# S151D.net
KiCad netlist of a schematic drawn in EAGLE
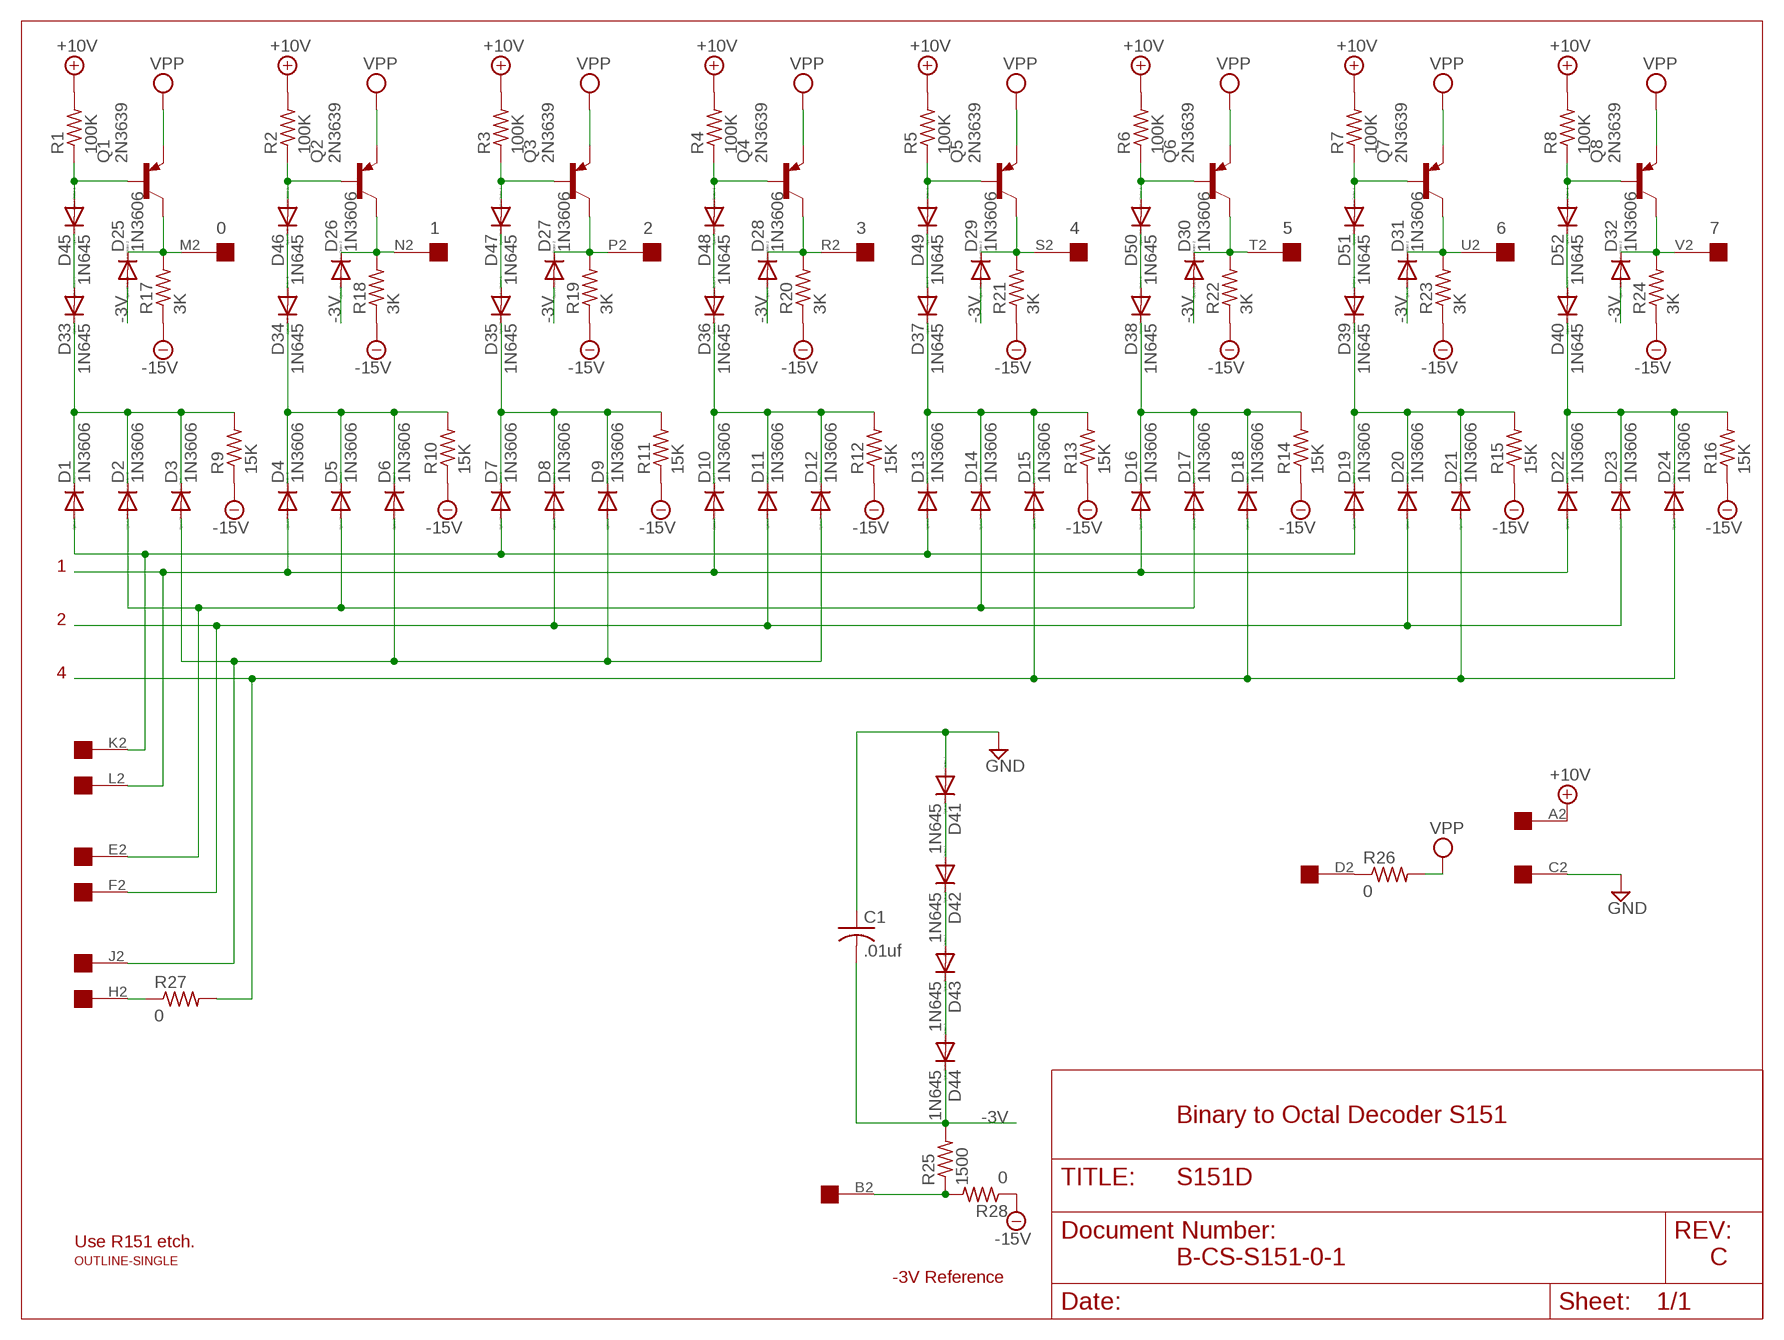
[diagram p0: schematic, sheet 1]

(export (version "E")
  (design (tool "Eeschema 10.0.6"))
  (components
    (comp (ref "C1")
      (value ".01uf")
      (footprint "eagle-import:C050-025X075")
      (libsource (lib "eagle-import") (part "C-US050-025X075"))
    )
    (comp (ref "D1")
      (value "1N3606")
      (footprint "eagle-import:DO35-10")
      (libsource (lib "eagle-import") (part "1N4148DO35-10"))
    )
    (comp (ref "D2")
      (value "1N3606")
      (footprint "eagle-import:DO35-10")
      (libsource (lib "eagle-import") (part "1N4148DO35-10"))
    )
    (comp (ref "D3")
      (value "1N3606")
      (footprint "eagle-import:DO35-10")
      (libsource (lib "eagle-import") (part "1N4148DO35-10"))
    )
    (comp (ref "D4")
      (value "1N3606")
      (footprint "eagle-import:DO35-10")
      (libsource (lib "eagle-import") (part "1N4148DO35-10"))
    )
    (comp (ref "D5")
      (value "1N3606")
      (footprint "eagle-import:DO35-10")
      (libsource (lib "eagle-import") (part "1N4148DO35-10"))
    )
    (comp (ref "D6")
      (value "1N3606")
      (footprint "eagle-import:DO35-10")
      (libsource (lib "eagle-import") (part "1N4148DO35-10"))
    )
    (comp (ref "D7")
      (value "1N3606")
      (footprint "eagle-import:DO35-10")
      (libsource (lib "eagle-import") (part "1N4148DO35-10"))
    )
    (comp (ref "D8")
      (value "1N3606")
      (footprint "eagle-import:DO35-10")
      (libsource (lib "eagle-import") (part "1N4148DO35-10"))
    )
    (comp (ref "D9")
      (value "1N3606")
      (footprint "eagle-import:DO35-10")
      (libsource (lib "eagle-import") (part "1N4148DO35-10"))
    )
    (comp (ref "D10")
      (value "1N3606")
      (footprint "eagle-import:DO35-10")
      (libsource (lib "eagle-import") (part "1N4148DO35-10"))
    )
    (comp (ref "D11")
      (value "1N3606")
      (footprint "eagle-import:DO35-10")
      (libsource (lib "eagle-import") (part "1N4148DO35-10"))
    )
    (comp (ref "D12")
      (value "1N3606")
      (footprint "eagle-import:DO35-10")
      (libsource (lib "eagle-import") (part "1N4148DO35-10"))
    )
    (comp (ref "D13")
      (value "1N3606")
      (footprint "eagle-import:DO35-10")
      (libsource (lib "eagle-import") (part "1N4148DO35-10"))
    )
    (comp (ref "D14")
      (value "1N3606")
      (footprint "eagle-import:DO35-10")
      (libsource (lib "eagle-import") (part "1N4148DO35-10"))
    )
    (comp (ref "D15")
      (value "1N3606")
      (footprint "eagle-import:DO35-10")
      (libsource (lib "eagle-import") (part "1N4148DO35-10"))
    )
    (comp (ref "D16")
      (value "1N3606")
      (footprint "eagle-import:DO35-10")
      (libsource (lib "eagle-import") (part "1N4148DO35-10"))
    )
    (comp (ref "D17")
      (value "1N3606")
      (footprint "eagle-import:DO35-10")
      (libsource (lib "eagle-import") (part "1N4148DO35-10"))
    )
    (comp (ref "D18")
      (value "1N3606")
      (footprint "eagle-import:DO35-10")
      (libsource (lib "eagle-import") (part "1N4148DO35-10"))
    )
    (comp (ref "D19")
      (value "1N3606")
      (footprint "eagle-import:DO35-10")
      (libsource (lib "eagle-import") (part "1N4148DO35-10"))
    )
    (comp (ref "D20")
      (value "1N3606")
      (footprint "eagle-import:DO35-10")
      (libsource (lib "eagle-import") (part "1N4148DO35-10"))
    )
    (comp (ref "D21")
      (value "1N3606")
      (footprint "eagle-import:DO35-10")
      (libsource (lib "eagle-import") (part "1N4148DO35-10"))
    )
    (comp (ref "D22")
      (value "1N3606")
      (footprint "eagle-import:DO35-10")
      (libsource (lib "eagle-import") (part "1N4148DO35-10"))
    )
    (comp (ref "D23")
      (value "1N3606")
      (footprint "eagle-import:DO35-10")
      (libsource (lib "eagle-import") (part "1N4148DO35-10"))
    )
    (comp (ref "D24")
      (value "1N3606")
      (footprint "eagle-import:DO35-10")
      (libsource (lib "eagle-import") (part "1N4148DO35-10"))
    )
    (comp (ref "D25")
      (value "1N3606")
      (footprint "eagle-import:DO35-10")
      (libsource (lib "eagle-import") (part "1N4148DO35-10"))
    )
    (comp (ref "D26")
      (value "1N3606")
      (footprint "eagle-import:DO35-10")
      (libsource (lib "eagle-import") (part "1N4148DO35-10"))
    )
    (comp (ref "D27")
      (value "1N3606")
      (footprint "eagle-import:DO35-10")
      (libsource (lib "eagle-import") (part "1N4148DO35-10"))
    )
    (comp (ref "D28")
      (value "1N3606")
      (footprint "eagle-import:DO35-10")
      (libsource (lib "eagle-import") (part "1N4148DO35-10"))
    )
    (comp (ref "D29")
      (value "1N3606")
      (footprint "eagle-import:DO35-10")
      (libsource (lib "eagle-import") (part "1N4148DO35-10"))
    )
    (comp (ref "D30")
      (value "1N3606")
      (footprint "eagle-import:DO35-10")
      (libsource (lib "eagle-import") (part "1N4148DO35-10"))
    )
    (comp (ref "D31")
      (value "1N3606")
      (footprint "eagle-import:DO35-10")
      (libsource (lib "eagle-import") (part "1N4148DO35-10"))
    )
    (comp (ref "D32")
      (value "1N3606")
      (footprint "eagle-import:DO35-10")
      (libsource (lib "eagle-import") (part "1N4148DO35-10"))
    )
    (comp (ref "D33")
      (value "1N645")
      (footprint "eagle-import:DO35-10")
      (libsource (lib "eagle-import") (part "1N4148DO35-10"))
    )
    (comp (ref "D34")
      (value "1N645")
      (footprint "eagle-import:DO35-10")
      (libsource (lib "eagle-import") (part "1N4148DO35-10"))
    )
    (comp (ref "D35")
      (value "1N645")
      (footprint "eagle-import:DO35-10")
      (libsource (lib "eagle-import") (part "1N4148DO35-10"))
    )
    (comp (ref "D36")
      (value "1N645")
      (footprint "eagle-import:DO35-10")
      (libsource (lib "eagle-import") (part "1N4148DO35-10"))
    )
    (comp (ref "D37")
      (value "1N645")
      (footprint "eagle-import:DO35-10")
      (libsource (lib "eagle-import") (part "1N4148DO35-10"))
    )
    (comp (ref "D38")
      (value "1N645")
      (footprint "eagle-import:DO35-10")
      (libsource (lib "eagle-import") (part "1N4148DO35-10"))
    )
    (comp (ref "D39")
      (value "1N645")
      (footprint "eagle-import:DO35-10")
      (libsource (lib "eagle-import") (part "1N4148DO35-10"))
    )
    (comp (ref "D40")
      (value "1N645")
      (footprint "eagle-import:DO35-10")
      (libsource (lib "eagle-import") (part "1N4148DO35-10"))
    )
    (comp (ref "D41")
      (value "1N645")
      (footprint "eagle-import:DO35-10")
      (libsource (lib "eagle-import") (part "1N4148DO35-10"))
    )
    (comp (ref "D42")
      (value "1N645")
      (footprint "eagle-import:DO35-10")
      (libsource (lib "eagle-import") (part "1N4148DO35-10"))
    )
    (comp (ref "D43")
      (value "1N645")
      (footprint "eagle-import:DO35-10")
      (libsource (lib "eagle-import") (part "1N4148DO35-10"))
    )
    (comp (ref "D44")
      (value "1N645")
      (footprint "eagle-import:DO35-10")
      (libsource (lib "eagle-import") (part "1N4148DO35-10"))
    )
    (comp (ref "D45")
      (value "1N645")
      (footprint "eagle-import:DO35-10")
      (libsource (lib "eagle-import") (part "1N4148DO35-10"))
    )
    (comp (ref "D46")
      (value "1N645")
      (footprint "eagle-import:DO35-10")
      (libsource (lib "eagle-import") (part "1N4148DO35-10"))
    )
    (comp (ref "D47")
      (value "1N645")
      (footprint "eagle-import:DO35-10")
      (libsource (lib "eagle-import") (part "1N4148DO35-10"))
    )
    (comp (ref "D48")
      (value "1N645")
      (footprint "eagle-import:DO35-10")
      (libsource (lib "eagle-import") (part "1N4148DO35-10"))
    )
    (comp (ref "D49")
      (value "1N645")
      (footprint "eagle-import:DO35-10")
      (libsource (lib "eagle-import") (part "1N4148DO35-10"))
    )
    (comp (ref "D50")
      (value "1N645")
      (footprint "eagle-import:DO35-10")
      (libsource (lib "eagle-import") (part "1N4148DO35-10"))
    )
    (comp (ref "D51")
      (value "1N645")
      (footprint "eagle-import:DO35-10")
      (libsource (lib "eagle-import") (part "1N4148DO35-10"))
    )
    (comp (ref "D52")
      (value "1N645")
      (footprint "eagle-import:DO35-10")
      (libsource (lib "eagle-import") (part "1N4148DO35-10"))
    )
    (comp (ref "Q1")
      (value "2N3639")
      (footprint "eagle-import:TO39")
      (libsource (lib "eagle-import") (part "2N3637"))
    )
    (comp (ref "Q2")
      (value "2N3639")
      (footprint "eagle-import:TO39")
      (libsource (lib "eagle-import") (part "2N3637"))
    )
    (comp (ref "Q3")
      (value "2N3639")
      (footprint "eagle-import:TO39")
      (libsource (lib "eagle-import") (part "2N3637"))
    )
    (comp (ref "Q4")
      (value "2N3639")
      (footprint "eagle-import:TO39")
      (libsource (lib "eagle-import") (part "2N3637"))
    )
    (comp (ref "Q5")
      (value "2N3639")
      (footprint "eagle-import:TO39")
      (libsource (lib "eagle-import") (part "2N3637"))
    )
    (comp (ref "Q6")
      (value "2N3639")
      (footprint "eagle-import:TO39")
      (libsource (lib "eagle-import") (part "2N3637"))
    )
    (comp (ref "Q7")
      (value "2N3639")
      (footprint "eagle-import:TO39")
      (libsource (lib "eagle-import") (part "2N3637"))
    )
    (comp (ref "Q8")
      (value "2N3639")
      (footprint "eagle-import:TO39")
      (libsource (lib "eagle-import") (part "2N3637"))
    )
    (comp (ref "R1")
      (value "100K")
      (footprint "eagle-import:0207_10")
      (libsource (lib "eagle-import") (part "R-US_0207/10"))
    )
    (comp (ref "R2")
      (value "100K")
      (footprint "eagle-import:0207_10")
      (libsource (lib "eagle-import") (part "R-US_0207/10"))
    )
    (comp (ref "R3")
      (value "100K")
      (footprint "eagle-import:0207_10")
      (libsource (lib "eagle-import") (part "R-US_0207/10"))
    )
    (comp (ref "R4")
      (value "100K")
      (footprint "eagle-import:0207_10")
      (libsource (lib "eagle-import") (part "R-US_0207/10"))
    )
    (comp (ref "R5")
      (value "100K")
      (footprint "eagle-import:0207_10")
      (libsource (lib "eagle-import") (part "R-US_0207/10"))
    )
    (comp (ref "R6")
      (value "100K")
      (footprint "eagle-import:0207_10")
      (libsource (lib "eagle-import") (part "R-US_0207/10"))
    )
    (comp (ref "R7")
      (value "100K")
      (footprint "eagle-import:0207_10")
      (libsource (lib "eagle-import") (part "R-US_0207/10"))
    )
    (comp (ref "R8")
      (value "100K")
      (footprint "eagle-import:0207_10")
      (libsource (lib "eagle-import") (part "R-US_0207/10"))
    )
    (comp (ref "R9")
      (value "15K")
      (footprint "eagle-import:0207_10")
      (libsource (lib "eagle-import") (part "R-US_0207/10"))
    )
    (comp (ref "R10")
      (value "15K")
      (footprint "eagle-import:0207_10")
      (libsource (lib "eagle-import") (part "R-US_0207/10"))
    )
    (comp (ref "R11")
      (value "15K")
      (footprint "eagle-import:0207_10")
      (libsource (lib "eagle-import") (part "R-US_0207/10"))
    )
    (comp (ref "R12")
      (value "15K")
      (footprint "eagle-import:0207_10")
      (libsource (lib "eagle-import") (part "R-US_0207/10"))
    )
    (comp (ref "R13")
      (value "15K")
      (footprint "eagle-import:0207_10")
      (libsource (lib "eagle-import") (part "R-US_0207/10"))
    )
    (comp (ref "R14")
      (value "15K")
      (footprint "eagle-import:0207_10")
      (libsource (lib "eagle-import") (part "R-US_0207/10"))
    )
    (comp (ref "R15")
      (value "15K")
      (footprint "eagle-import:0207_10")
      (libsource (lib "eagle-import") (part "R-US_0207/10"))
    )
    (comp (ref "R16")
      (value "15K")
      (footprint "eagle-import:0207_10")
      (libsource (lib "eagle-import") (part "R-US_0207/10"))
    )
    (comp (ref "R17")
      (value "3K")
      (footprint "eagle-import:0207_10")
      (libsource (lib "eagle-import") (part "R-US_0207/10"))
    )
    (comp (ref "R18")
      (value "3K")
      (footprint "eagle-import:0207_10")
      (libsource (lib "eagle-import") (part "R-US_0207/10"))
    )
    (comp (ref "R19")
      (value "3K")
      (footprint "eagle-import:0207_10")
      (libsource (lib "eagle-import") (part "R-US_0207/10"))
    )
    (comp (ref "R20")
      (value "3K")
      (footprint "eagle-import:0207_10")
      (libsource (lib "eagle-import") (part "R-US_0207/10"))
    )
    (comp (ref "R21")
      (value "3K")
      (footprint "eagle-import:0207_10")
      (libsource (lib "eagle-import") (part "R-US_0207/10"))
    )
    (comp (ref "R22")
      (value "3K")
      (footprint "eagle-import:0207_10")
      (libsource (lib "eagle-import") (part "R-US_0207/10"))
    )
    (comp (ref "R23")
      (value "3K")
      (footprint "eagle-import:0207_10")
      (libsource (lib "eagle-import") (part "R-US_0207/10"))
    )
    (comp (ref "R24")
      (value "3K")
      (footprint "eagle-import:0207_10")
      (libsource (lib "eagle-import") (part "R-US_0207/10"))
    )
    (comp (ref "R25")
      (value "1500")
      (footprint "eagle-import:0207_10")
      (libsource (lib "eagle-import") (part "R-US_0207/10"))
    )
    (comp (ref "R26")
      (value "0")
      (footprint "eagle-import:0207_10")
      (libsource (lib "eagle-import") (part "R-US_0207/10"))
    )
    (comp (ref "R27")
      (value "0")
      (footprint "eagle-import:0207_10")
      (libsource (lib "eagle-import") (part "R-US_0207/10"))
    )
    (comp (ref "R28")
      (value "0")
      (footprint "eagle-import:0207_10")
      (libsource (lib "eagle-import") (part "R-US_0207/10"))
    )
    (comp (ref "U$1")
      (value "OUTLINE-SINGLE")
      (footprint "eagle-import:SINGLE")
      (libsource (lib "eagle-import") (part "OUTLINE-SINGLE"))
    )
    (comp (ref "U$2")
      (value "EDGE-1")
      (footprint "eagle-import:EDGE-CON1")
      (libsource (lib "eagle-import") (part "EDGE-1"))
    )
  )
  (nets
    (net (code "1") (name "+10V") (class "Default")
      (node (ref "R1") (pin "2") (pinfunction "2_2") (pintype "passive"))
      (node (ref "R2") (pin "2") (pinfunction "2_2") (pintype "passive"))
      (node (ref "R3") (pin "2") (pinfunction "2_2") (pintype "passive"))
      (node (ref "R4") (pin "2") (pinfunction "2_2") (pintype "passive"))
      (node (ref "R5") (pin "2") (pinfunction "2_2") (pintype "passive"))
      (node (ref "R6") (pin "2") (pinfunction "2_2") (pintype "passive"))
      (node (ref "R7") (pin "2") (pinfunction "2_2") (pintype "passive"))
      (node (ref "R8") (pin "2") (pinfunction "2_2") (pintype "passive"))
      (node (ref "U$2") (pin "A2") (pinfunction "1_A2") (pintype "bidirectional"))
    )
    (net (code "2") (name "-15V") (class "Default")
      (node (ref "R10") (pin "1") (pinfunction "1_1") (pintype "passive"))
      (node (ref "R11") (pin "1") (pinfunction "1_1") (pintype "passive"))
      (node (ref "R12") (pin "1") (pinfunction "1_1") (pintype "passive"))
      (node (ref "R13") (pin "1") (pinfunction "1_1") (pintype "passive"))
      (node (ref "R14") (pin "1") (pinfunction "1_1") (pintype "passive"))
      (node (ref "R15") (pin "1") (pinfunction "1_1") (pintype "passive"))
      (node (ref "R16") (pin "1") (pinfunction "1_1") (pintype "passive"))
      (node (ref "R17") (pin "1") (pinfunction "1_1") (pintype "passive"))
      (node (ref "R18") (pin "1") (pinfunction "1_1") (pintype "passive"))
      (node (ref "R19") (pin "1") (pinfunction "1_1") (pintype "passive"))
      (node (ref "R20") (pin "1") (pinfunction "1_1") (pintype "passive"))
      (node (ref "R21") (pin "1") (pinfunction "1_1") (pintype "passive"))
      (node (ref "R22") (pin "1") (pinfunction "1_1") (pintype "passive"))
      (node (ref "R23") (pin "1") (pinfunction "1_1") (pintype "passive"))
      (node (ref "R24") (pin "1") (pinfunction "1_1") (pintype "passive"))
      (node (ref "R28") (pin "1") (pinfunction "1_1") (pintype "passive"))
      (node (ref "R9") (pin "1") (pinfunction "1_1") (pintype "passive"))
    )
    (net (code "3") (name "/-3V") (class "Default")
      (node (ref "C1") (pin "2") (pinfunction "2_2") (pintype "passive"))
      (node (ref "D25") (pin "A") (pinfunction "A_A") (pintype "passive"))
      (node (ref "D26") (pin "A") (pinfunction "A_A") (pintype "passive"))
      (node (ref "D27") (pin "A") (pinfunction "A_A") (pintype "passive"))
      (node (ref "D28") (pin "A") (pinfunction "A_A") (pintype "passive"))
      (node (ref "D29") (pin "A") (pinfunction "A_A") (pintype "passive"))
      (node (ref "D30") (pin "A") (pinfunction "A_A") (pintype "passive"))
      (node (ref "D31") (pin "A") (pinfunction "A_A") (pintype "passive"))
      (node (ref "D32") (pin "A") (pinfunction "A_A") (pintype "passive"))
      (node (ref "D44") (pin "C") (pinfunction "C_C") (pintype "passive"))
      (node (ref "R25") (pin "2") (pinfunction "2_2") (pintype "passive"))
    )
    (net (code "4") (name "/0") (class "Default")
      (node (ref "D25") (pin "C") (pinfunction "C_C") (pintype "passive"))
      (node (ref "Q1") (pin "3") (pinfunction "C_3") (pintype "passive"))
      (node (ref "R17") (pin "2") (pinfunction "2_2") (pintype "passive"))
      (node (ref "U$2") (pin "M2") (pinfunction "1_M2") (pintype "bidirectional"))
    )
    (net (code "5") (name "/1") (class "Default")
      (node (ref "D26") (pin "C") (pinfunction "C_C") (pintype "passive"))
      (node (ref "Q2") (pin "3") (pinfunction "C_3") (pintype "passive"))
      (node (ref "R18") (pin "2") (pinfunction "2_2") (pintype "passive"))
      (node (ref "U$2") (pin "N2") (pinfunction "1_N2") (pintype "bidirectional"))
    )
    (net (code "6") (name "/2") (class "Default")
      (node (ref "D27") (pin "C") (pinfunction "C_C") (pintype "passive"))
      (node (ref "Q3") (pin "3") (pinfunction "C_3") (pintype "passive"))
      (node (ref "R19") (pin "2") (pinfunction "2_2") (pintype "passive"))
      (node (ref "U$2") (pin "P2") (pinfunction "1_P2") (pintype "bidirectional"))
    )
    (net (code "7") (name "/3") (class "Default")
      (node (ref "D28") (pin "C") (pinfunction "C_C") (pintype "passive"))
      (node (ref "Q4") (pin "3") (pinfunction "C_3") (pintype "passive"))
      (node (ref "R20") (pin "2") (pinfunction "2_2") (pintype "passive"))
      (node (ref "U$2") (pin "R2") (pinfunction "1_R2") (pintype "bidirectional"))
    )
    (net (code "8") (name "/4") (class "Default")
      (node (ref "D29") (pin "C") (pinfunction "C_C") (pintype "passive"))
      (node (ref "Q5") (pin "3") (pinfunction "C_3") (pintype "passive"))
      (node (ref "R21") (pin "2") (pinfunction "2_2") (pintype "passive"))
      (node (ref "U$2") (pin "S2") (pinfunction "1_S2") (pintype "bidirectional"))
    )
    (net (code "9") (name "/5") (class "Default")
      (node (ref "D30") (pin "C") (pinfunction "C_C") (pintype "passive"))
      (node (ref "Q6") (pin "3") (pinfunction "C_3") (pintype "passive"))
      (node (ref "R22") (pin "2") (pinfunction "2_2") (pintype "passive"))
      (node (ref "U$2") (pin "T2") (pinfunction "1_T2") (pintype "bidirectional"))
    )
    (net (code "10") (name "/6") (class "Default")
      (node (ref "D31") (pin "C") (pinfunction "C_C") (pintype "passive"))
      (node (ref "Q7") (pin "3") (pinfunction "C_3") (pintype "passive"))
      (node (ref "R23") (pin "2") (pinfunction "2_2") (pintype "passive"))
      (node (ref "U$2") (pin "U2") (pinfunction "1_U2") (pintype "bidirectional"))
    )
    (net (code "11") (name "/7") (class "Default")
      (node (ref "D32") (pin "C") (pinfunction "C_C") (pintype "passive"))
      (node (ref "Q8") (pin "3") (pinfunction "C_3") (pintype "passive"))
      (node (ref "R24") (pin "2") (pinfunction "2_2") (pintype "passive"))
      (node (ref "U$2") (pin "V2") (pinfunction "1_V2") (pintype "bidirectional"))
    )
    (net (code "12") (name "GND") (class "Default")
      (node (ref "C1") (pin "1") (pinfunction "1_1") (pintype "passive"))
      (node (ref "D41") (pin "A") (pinfunction "A_A") (pintype "passive"))
      (node (ref "U$2") (pin "C2") (pinfunction "1_C2") (pintype "bidirectional"))
    )
    (net (code "13") (name "Net-(D1-PadC)") (class "Default")
      (node (ref "D1") (pin "C") (pinfunction "C_C") (pintype "passive"))
      (node (ref "D2") (pin "C") (pinfunction "C_C") (pintype "passive"))
      (node (ref "D3") (pin "C") (pinfunction "C_C") (pintype "passive"))
      (node (ref "D33") (pin "C") (pinfunction "C_C") (pintype "passive"))
      (node (ref "R9") (pin "2") (pinfunction "2_2") (pintype "passive"))
    )
    (net (code "14") (name "Net-(D10-PadC)") (class "Default")
      (node (ref "D10") (pin "C") (pinfunction "C_C") (pintype "passive"))
      (node (ref "D11") (pin "C") (pinfunction "C_C") (pintype "passive"))
      (node (ref "D12") (pin "C") (pinfunction "C_C") (pintype "passive"))
      (node (ref "D36") (pin "C") (pinfunction "C_C") (pintype "passive"))
      (node (ref "R12") (pin "2") (pinfunction "2_2") (pintype "passive"))
    )
    (net (code "15") (name "Net-(D13-PadC)") (class "Default")
      (node (ref "D13") (pin "C") (pinfunction "C_C") (pintype "passive"))
      (node (ref "D14") (pin "C") (pinfunction "C_C") (pintype "passive"))
      (node (ref "D15") (pin "C") (pinfunction "C_C") (pintype "passive"))
      (node (ref "D37") (pin "C") (pinfunction "C_C") (pintype "passive"))
      (node (ref "R13") (pin "2") (pinfunction "2_2") (pintype "passive"))
    )
    (net (code "16") (name "Net-(D15-PadA)") (class "Default")
      (node (ref "D15") (pin "A") (pinfunction "A_A") (pintype "passive"))
      (node (ref "D18") (pin "A") (pinfunction "A_A") (pintype "passive"))
      (node (ref "D21") (pin "A") (pinfunction "A_A") (pintype "passive"))
      (node (ref "D24") (pin "A") (pinfunction "A_A") (pintype "passive"))
      (node (ref "R27") (pin "2") (pinfunction "2_2") (pintype "passive"))
    )
    (net (code "17") (name "Net-(D16-PadC)") (class "Default")
      (node (ref "D16") (pin "C") (pinfunction "C_C") (pintype "passive"))
      (node (ref "D17") (pin "C") (pinfunction "C_C") (pintype "passive"))
      (node (ref "D18") (pin "C") (pinfunction "C_C") (pintype "passive"))
      (node (ref "D38") (pin "C") (pinfunction "C_C") (pintype "passive"))
      (node (ref "R14") (pin "2") (pinfunction "2_2") (pintype "passive"))
    )
    (net (code "18") (name "Net-(D19-PadC)") (class "Default")
      (node (ref "D19") (pin "C") (pinfunction "C_C") (pintype "passive"))
      (node (ref "D20") (pin "C") (pinfunction "C_C") (pintype "passive"))
      (node (ref "D21") (pin "C") (pinfunction "C_C") (pintype "passive"))
      (node (ref "D39") (pin "C") (pinfunction "C_C") (pintype "passive"))
      (node (ref "R15") (pin "2") (pinfunction "2_2") (pintype "passive"))
    )
    (net (code "19") (name "Net-(D22-PadC)") (class "Default")
      (node (ref "D22") (pin "C") (pinfunction "C_C") (pintype "passive"))
      (node (ref "D23") (pin "C") (pinfunction "C_C") (pintype "passive"))
      (node (ref "D24") (pin "C") (pinfunction "C_C") (pintype "passive"))
      (node (ref "D40") (pin "C") (pinfunction "C_C") (pintype "passive"))
      (node (ref "R16") (pin "2") (pinfunction "2_2") (pintype "passive"))
    )
    (net (code "20") (name "Net-(D33-PadA)") (class "Default")
      (node (ref "D33") (pin "A") (pinfunction "A_A") (pintype "passive"))
      (node (ref "D45") (pin "C") (pinfunction "C_C") (pintype "passive"))
    )
    (net (code "21") (name "Net-(D34-PadA)") (class "Default")
      (node (ref "D34") (pin "A") (pinfunction "A_A") (pintype "passive"))
      (node (ref "D46") (pin "C") (pinfunction "C_C") (pintype "passive"))
    )
    (net (code "22") (name "Net-(D34-PadC)") (class "Default")
      (node (ref "D34") (pin "C") (pinfunction "C_C") (pintype "passive"))
      (node (ref "D4") (pin "C") (pinfunction "C_C") (pintype "passive"))
      (node (ref "D5") (pin "C") (pinfunction "C_C") (pintype "passive"))
      (node (ref "D6") (pin "C") (pinfunction "C_C") (pintype "passive"))
      (node (ref "R10") (pin "2") (pinfunction "2_2") (pintype "passive"))
    )
    (net (code "23") (name "Net-(D35-PadA)") (class "Default")
      (node (ref "D35") (pin "A") (pinfunction "A_A") (pintype "passive"))
      (node (ref "D47") (pin "C") (pinfunction "C_C") (pintype "passive"))
    )
    (net (code "24") (name "Net-(D35-PadC)") (class "Default")
      (node (ref "D35") (pin "C") (pinfunction "C_C") (pintype "passive"))
      (node (ref "D7") (pin "C") (pinfunction "C_C") (pintype "passive"))
      (node (ref "D8") (pin "C") (pinfunction "C_C") (pintype "passive"))
      (node (ref "D9") (pin "C") (pinfunction "C_C") (pintype "passive"))
      (node (ref "R11") (pin "2") (pinfunction "2_2") (pintype "passive"))
    )
    (net (code "25") (name "Net-(D36-PadA)") (class "Default")
      (node (ref "D36") (pin "A") (pinfunction "A_A") (pintype "passive"))
      (node (ref "D48") (pin "C") (pinfunction "C_C") (pintype "passive"))
    )
    (net (code "26") (name "Net-(D37-PadA)") (class "Default")
      (node (ref "D37") (pin "A") (pinfunction "A_A") (pintype "passive"))
      (node (ref "D49") (pin "C") (pinfunction "C_C") (pintype "passive"))
    )
    (net (code "27") (name "Net-(D38-PadA)") (class "Default")
      (node (ref "D38") (pin "A") (pinfunction "A_A") (pintype "passive"))
      (node (ref "D50") (pin "C") (pinfunction "C_C") (pintype "passive"))
    )
    (net (code "28") (name "Net-(D39-PadA)") (class "Default")
      (node (ref "D39") (pin "A") (pinfunction "A_A") (pintype "passive"))
      (node (ref "D51") (pin "C") (pinfunction "C_C") (pintype "passive"))
    )
    (net (code "29") (name "Net-(D40-PadA)") (class "Default")
      (node (ref "D40") (pin "A") (pinfunction "A_A") (pintype "passive"))
      (node (ref "D52") (pin "C") (pinfunction "C_C") (pintype "passive"))
    )
    (net (code "30") (name "Net-(D41-PadC)") (class "Default")
      (node (ref "D41") (pin "C") (pinfunction "C_C") (pintype "passive"))
      (node (ref "D42") (pin "A") (pinfunction "A_A") (pintype "passive"))
    )
    (net (code "31") (name "Net-(D42-PadC)") (class "Default")
      (node (ref "D42") (pin "C") (pinfunction "C_C") (pintype "passive"))
      (node (ref "D43") (pin "A") (pinfunction "A_A") (pintype "passive"))
    )
    (net (code "32") (name "Net-(D43-PadC)") (class "Default")
      (node (ref "D43") (pin "C") (pinfunction "C_C") (pintype "passive"))
      (node (ref "D44") (pin "A") (pinfunction "A_A") (pintype "passive"))
    )
    (net (code "33") (name "Net-(Q1-B)") (class "Default")
      (node (ref "D45") (pin "A") (pinfunction "A_A") (pintype "passive"))
      (node (ref "Q1") (pin "2") (pinfunction "B_2") (pintype "passive"))
      (node (ref "R1") (pin "1") (pinfunction "1_1") (pintype "passive"))
    )
    (net (code "34") (name "Net-(Q2-B)") (class "Default")
      (node (ref "D46") (pin "A") (pinfunction "A_A") (pintype "passive"))
      (node (ref "Q2") (pin "2") (pinfunction "B_2") (pintype "passive"))
      (node (ref "R2") (pin "1") (pinfunction "1_1") (pintype "passive"))
    )
    (net (code "35") (name "Net-(Q3-B)") (class "Default")
      (node (ref "D47") (pin "A") (pinfunction "A_A") (pintype "passive"))
      (node (ref "Q3") (pin "2") (pinfunction "B_2") (pintype "passive"))
      (node (ref "R3") (pin "1") (pinfunction "1_1") (pintype "passive"))
    )
    (net (code "36") (name "Net-(Q4-B)") (class "Default")
      (node (ref "D48") (pin "A") (pinfunction "A_A") (pintype "passive"))
      (node (ref "Q4") (pin "2") (pinfunction "B_2") (pintype "passive"))
      (node (ref "R4") (pin "1") (pinfunction "1_1") (pintype "passive"))
    )
    (net (code "37") (name "Net-(Q5-B)") (class "Default")
      (node (ref "D49") (pin "A") (pinfunction "A_A") (pintype "passive"))
      (node (ref "Q5") (pin "2") (pinfunction "B_2") (pintype "passive"))
      (node (ref "R5") (pin "1") (pinfunction "1_1") (pintype "passive"))
    )
    (net (code "38") (name "Net-(Q6-B)") (class "Default")
      (node (ref "D50") (pin "A") (pinfunction "A_A") (pintype "passive"))
      (node (ref "Q6") (pin "2") (pinfunction "B_2") (pintype "passive"))
      (node (ref "R6") (pin "1") (pinfunction "1_1") (pintype "passive"))
    )
    (net (code "39") (name "Net-(Q7-B)") (class "Default")
      (node (ref "D51") (pin "A") (pinfunction "A_A") (pintype "passive"))
      (node (ref "Q7") (pin "2") (pinfunction "B_2") (pintype "passive"))
      (node (ref "R7") (pin "1") (pinfunction "1_1") (pintype "passive"))
    )
    (net (code "40") (name "Net-(Q8-B)") (class "Default")
      (node (ref "D52") (pin "A") (pinfunction "A_A") (pintype "passive"))
      (node (ref "Q8") (pin "2") (pinfunction "B_2") (pintype "passive"))
      (node (ref "R8") (pin "1") (pinfunction "1_1") (pintype "passive"))
    )
    (net (code "41") (name "Net-(U$2B-1)") (class "Default")
      (node (ref "R25") (pin "1") (pinfunction "1_1") (pintype "passive"))
      (node (ref "R28") (pin "2") (pinfunction "2_2") (pintype "passive"))
      (node (ref "U$2") (pin "B2") (pinfunction "1_B2") (pintype "bidirectional"))
    )
    (net (code "42") (name "Net-(U$2D-1)") (class "Default")
      (node (ref "R26") (pin "1") (pinfunction "1_1") (pintype "passive"))
      (node (ref "U$2") (pin "D2") (pinfunction "1_D2") (pintype "bidirectional"))
    )
    (net (code "43") (name "Net-(U$2E-1)") (class "Default")
      (node (ref "D14") (pin "A") (pinfunction "A_A") (pintype "passive"))
      (node (ref "D17") (pin "A") (pinfunction "A_A") (pintype "passive"))
      (node (ref "D2") (pin "A") (pinfunction "A_A") (pintype "passive"))
      (node (ref "D5") (pin "A") (pinfunction "A_A") (pintype "passive"))
      (node (ref "U$2") (pin "E2") (pinfunction "1_E2") (pintype "bidirectional"))
    )
    (net (code "44") (name "Net-(U$2F-1)") (class "Default")
      (node (ref "D11") (pin "A") (pinfunction "A_A") (pintype "passive"))
      (node (ref "D20") (pin "A") (pinfunction "A_A") (pintype "passive"))
      (node (ref "D23") (pin "A") (pinfunction "A_A") (pintype "passive"))
      (node (ref "D8") (pin "A") (pinfunction "A_A") (pintype "passive"))
      (node (ref "U$2") (pin "F2") (pinfunction "1_F2") (pintype "bidirectional"))
    )
    (net (code "45") (name "Net-(U$2G-1)") (class "Default")
      (node (ref "R27") (pin "1") (pinfunction "1_1") (pintype "passive"))
      (node (ref "U$2") (pin "H2") (pinfunction "1_H2") (pintype "bidirectional"))
    )
    (net (code "46") (name "Net-(U$2H-1)") (class "Default")
      (node (ref "D12") (pin "A") (pinfunction "A_A") (pintype "passive"))
      (node (ref "D3") (pin "A") (pinfunction "A_A") (pintype "passive"))
      (node (ref "D6") (pin "A") (pinfunction "A_A") (pintype "passive"))
      (node (ref "D9") (pin "A") (pinfunction "A_A") (pintype "passive"))
      (node (ref "U$2") (pin "J2") (pinfunction "1_J2") (pintype "bidirectional"))
    )
    (net (code "47") (name "Net-(U$2I-1)") (class "Default")
      (node (ref "D1") (pin "A") (pinfunction "A_A") (pintype "passive"))
      (node (ref "D13") (pin "A") (pinfunction "A_A") (pintype "passive"))
      (node (ref "D19") (pin "A") (pinfunction "A_A") (pintype "passive"))
      (node (ref "D7") (pin "A") (pinfunction "A_A") (pintype "passive"))
      (node (ref "U$2") (pin "K2") (pinfunction "1_K2") (pintype "bidirectional"))
    )
    (net (code "48") (name "Net-(U$2J-1)") (class "Default")
      (node (ref "D10") (pin "A") (pinfunction "A_A") (pintype "passive"))
      (node (ref "D16") (pin "A") (pinfunction "A_A") (pintype "passive"))
      (node (ref "D22") (pin "A") (pinfunction "A_A") (pintype "passive"))
      (node (ref "D4") (pin "A") (pinfunction "A_A") (pintype "passive"))
      (node (ref "U$2") (pin "L2") (pinfunction "1_L2") (pintype "bidirectional"))
    )
    (net (code "49") (name "VPP") (class "Default")
      (node (ref "Q1") (pin "1") (pinfunction "E_1") (pintype "passive"))
      (node (ref "Q2") (pin "1") (pinfunction "E_1") (pintype "passive"))
      (node (ref "Q3") (pin "1") (pinfunction "E_1") (pintype "passive"))
      (node (ref "Q4") (pin "1") (pinfunction "E_1") (pintype "passive"))
      (node (ref "Q5") (pin "1") (pinfunction "E_1") (pintype "passive"))
      (node (ref "Q6") (pin "1") (pinfunction "E_1") (pintype "passive"))
      (node (ref "Q7") (pin "1") (pinfunction "E_1") (pintype "passive"))
      (node (ref "Q8") (pin "1") (pinfunction "E_1") (pintype "passive"))
      (node (ref "R26") (pin "2") (pinfunction "2_2") (pintype "passive"))
    )
  )
)
